# Power_Switching_Circuit_rev2.net
KiCad netlist of a schematic drawn in EAGLE
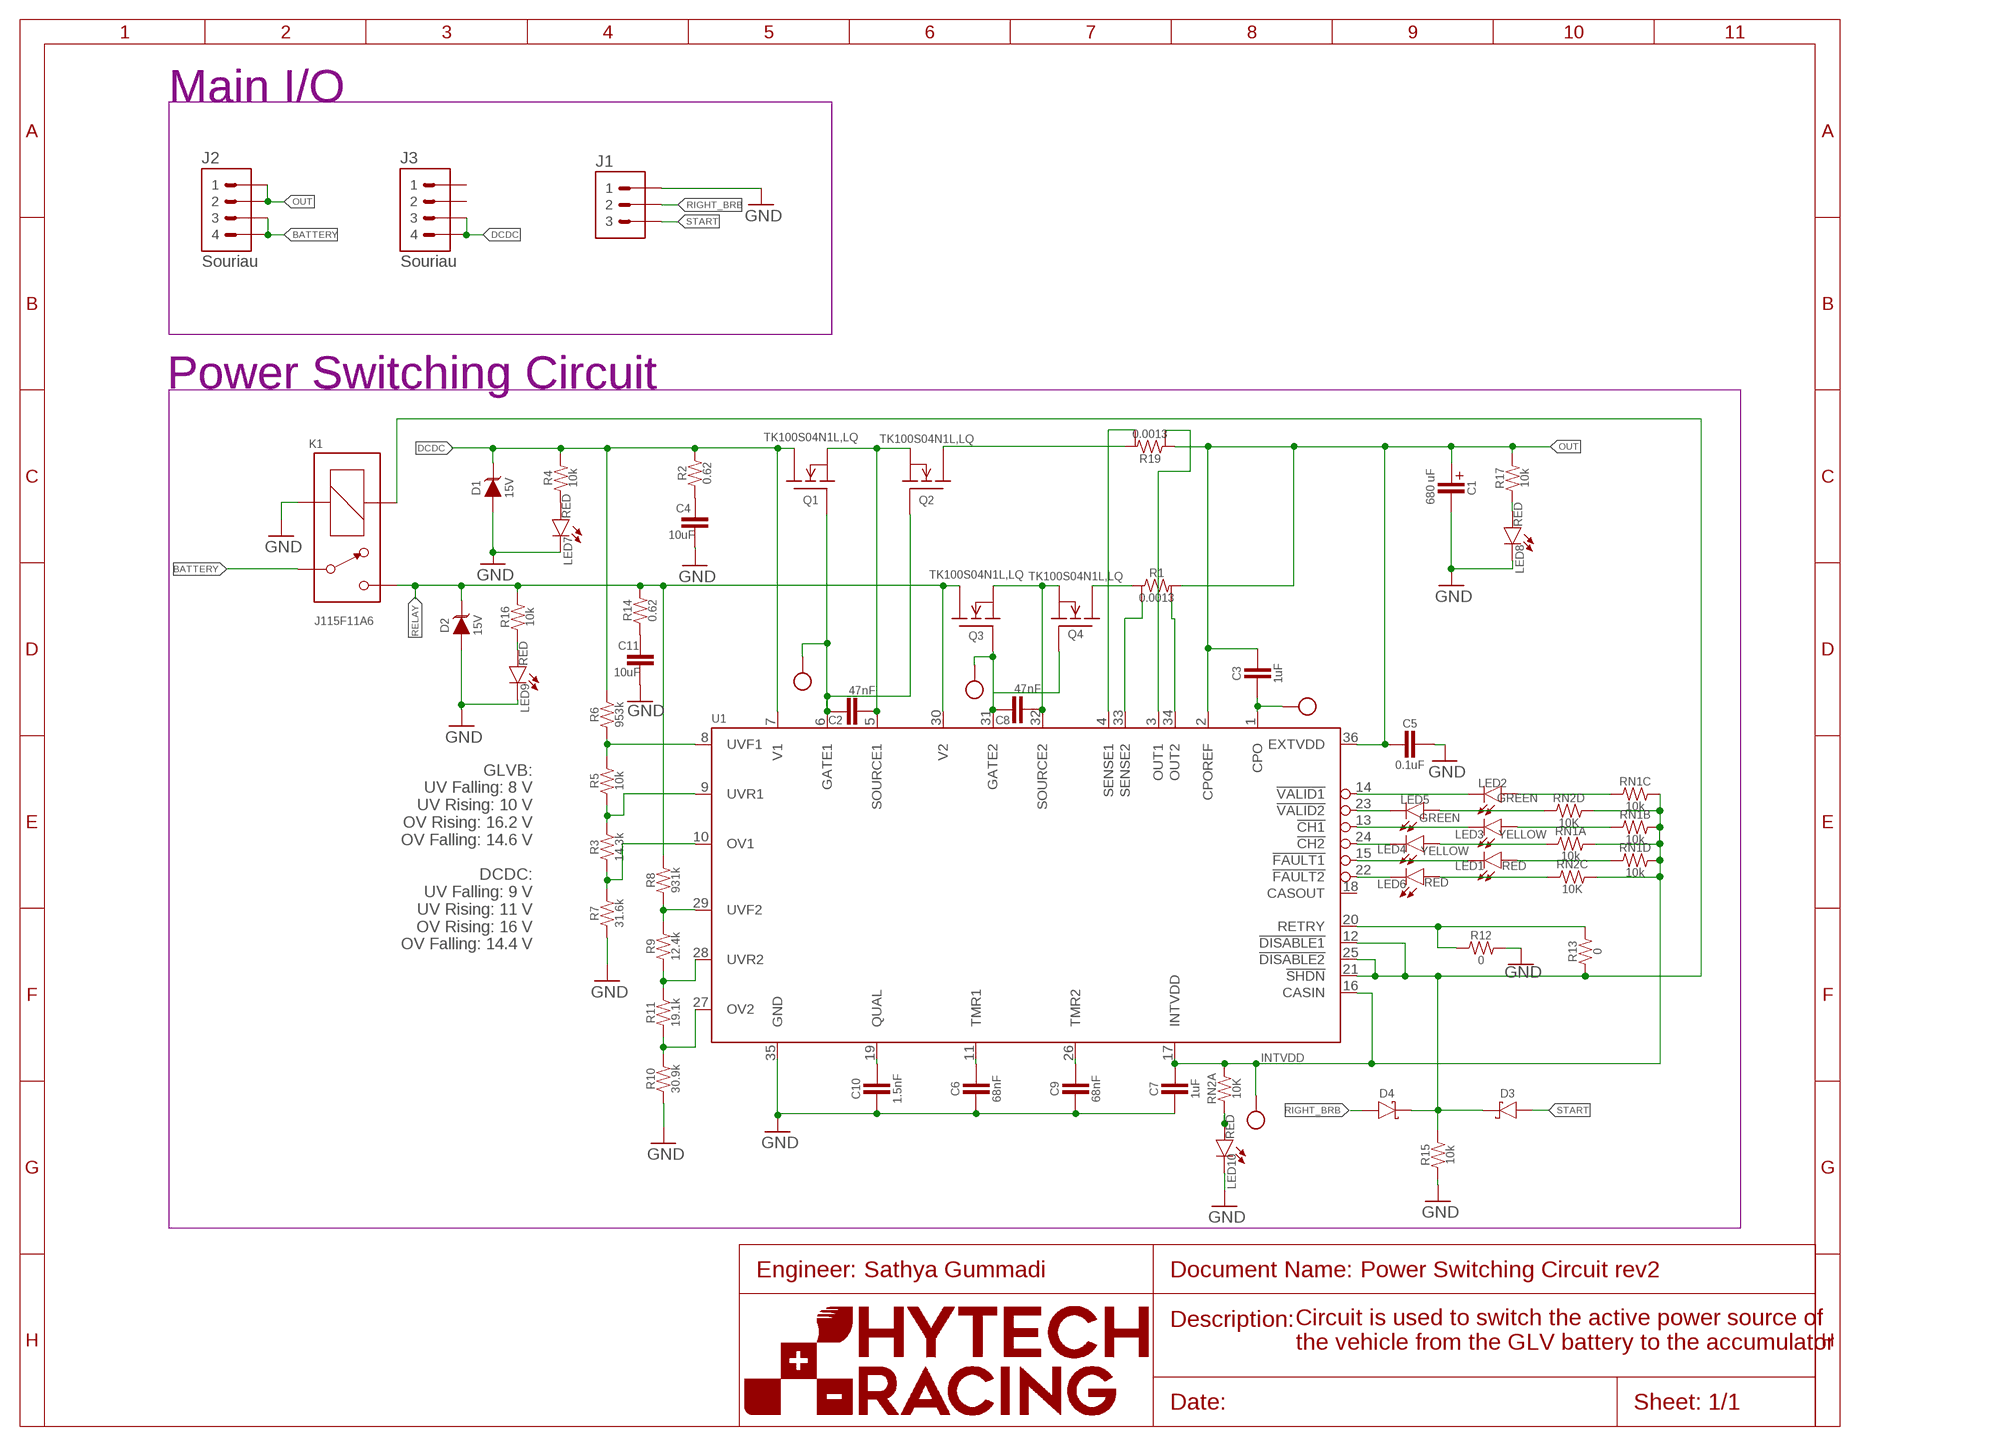
[diagram p0: schematic, sheet 1]

(export (version "E")
  (design (tool "Eeschema 10.0.6"))
  (components
    (comp (ref "C1")
      (value "CAPACITOR_POLARIZED")
      (footprint "eagle-import:EEE-FK1H681AM")
      (libsource (lib "eagle-import") (part "CAPACITOR_POLARIZED"))
    )
    (comp (ref "C2")
      (value "47nF")
      (footprint "eagle-import:0603-CAP@1")
      (libsource (lib "eagle-import") (part "CAP0603-CAP"))
    )
    (comp (ref "C3")
      (value "1uF")
      (footprint "eagle-import:0805")
      (libsource (lib "eagle-import") (part "CAP0805"))
    )
    (comp (ref "C4")
      (value "10uF")
      (footprint "eagle-import:1206-CAP")
      (libsource (lib "eagle-import") (part "CAPACITOR_VALUE1206"))
    )
    (comp (ref "C5")
      (value "0.1uF")
      (footprint "eagle-import:0603-CAP@1")
      (libsource (lib "eagle-import") (part "CAP0603-CAP"))
    )
    (comp (ref "C6")
      (value "68nF")
      (footprint "eagle-import:0603-CAP@1")
      (libsource (lib "eagle-import") (part "CAP0603-CAP"))
    )
    (comp (ref "C7")
      (value "1uF")
      (footprint "eagle-import:0805")
      (libsource (lib "eagle-import") (part "CAP0805"))
    )
    (comp (ref "C8")
      (value "47nF")
      (footprint "eagle-import:0603-CAP@1")
      (libsource (lib "eagle-import") (part "CAP0603-CAP"))
    )
    (comp (ref "C9")
      (value "68nF")
      (footprint "eagle-import:0603-CAP@1")
      (libsource (lib "eagle-import") (part "CAP0603-CAP"))
    )
    (comp (ref "C10")
      (value "1.5nF")
      (footprint "eagle-import:0603-CAP@1")
      (libsource (lib "eagle-import") (part "CAP0603-CAP"))
    )
    (comp (ref "C11")
      (value "10uF")
      (footprint "eagle-import:1206-CAP")
      (libsource (lib "eagle-import") (part "CAPACITOR_VALUE1206"))
    )
    (comp (ref "D1")
      (value "TVS_15V")
      (footprint "eagle-import:SOT-23")
      (fields
        (field (name "MANUFACTURER") "Vishay General Semiconductor - Diodes Division")
        (field (name "MPN") "GSOT15-E3-08")
        (field (name "VOLTAGE") "15V")
      )
      (libsource (lib "eagle-import") (part "TVS_15V"))
    )
    (comp (ref "D2")
      (value "TVS_15V")
      (footprint "eagle-import:SOT-23")
      (fields
        (field (name "MANUFACTURER") "Vishay General Semiconductor - Diodes Division")
        (field (name "MPN") "GSOT15-E3-08")
        (field (name "VOLTAGE") "15V")
      )
      (libsource (lib "eagle-import") (part "TVS_15V"))
    )
    (comp (ref "D3")
      (value "SCHOTTKY")
      (footprint "eagle-import:CLP1608-2L")
      (fields
        (field (name "MANUFACTURER") "Vishay General Semiconductor - Diodes Division")
        (field (name "MPN") "VSKY20401608-G4-08")
      )
      (libsource (lib "eagle-import") (part "SCHOTTKY"))
    )
    (comp (ref "D4")
      (value "SCHOTTKY")
      (footprint "eagle-import:CLP1608-2L")
      (fields
        (field (name "MANUFACTURER") "Vishay General Semiconductor - Diodes Division")
        (field (name "MPN") "VSKY20401608-G4-08")
      )
      (libsource (lib "eagle-import") (part "SCHOTTKY"))
    )
    (comp (ref "J1")
      (value "CONNECTOR-3_")
      (footprint "eagle-import:SOURIAU_04-35")
      (libsource (lib "eagle-import") (part "CONNECTOR-3_?"))
    )
    (comp (ref "J2")
      (value "CONNECTOR-4_SOURIAU_")
      (footprint "eagle-import:SOURIAU_12-04")
      (fields
        (field (name "MODEL") "Souriau")
        (field (name "MANUFACTURER") "Souriau")
        (field (name "MPN") "8STA21204PN ")
      )
      (libsource (lib "eagle-import") (part "CONNECTOR-4_?_SOURIAU"))
    )
    (comp (ref "J3")
      (value "CONNECTOR-4_SOURIAU_")
      (footprint "eagle-import:SOURIAU_12-04")
      (fields
        (field (name "MODEL") "Souriau")
        (field (name "MANUFACTURER") "Souriau")
        (field (name "MPN") "8STA21204PN ")
      )
      (libsource (lib "eagle-import") (part "CONNECTOR-4_?_SOURIAU"))
    )
    (comp (ref "K1")
      (value "J115F11A6")
      (footprint "eagle-import:J115F11A_6_")
      (libsource (lib "eagle-import") (part "J115F11A6"))
    )
    (comp (ref "LED1")
      (value "RED")
      (footprint "eagle-import:LED-603")
      (libsource (lib "eagle-import") (part "LED-0603"))
    )
    (comp (ref "LED2")
      (value "GREEN")
      (footprint "eagle-import:LED-603")
      (libsource (lib "eagle-import") (part "LED-0603"))
    )
    (comp (ref "LED3")
      (value "YELLOW")
      (footprint "eagle-import:LED-603")
      (libsource (lib "eagle-import") (part "LED-0603"))
    )
    (comp (ref "LED4")
      (value "YELLOW")
      (footprint "eagle-import:LED-603")
      (libsource (lib "eagle-import") (part "LED-0603"))
    )
    (comp (ref "LED5")
      (value "GREEN")
      (footprint "eagle-import:LED-603")
      (libsource (lib "eagle-import") (part "LED-0603"))
    )
    (comp (ref "LED6")
      (value "RED")
      (footprint "eagle-import:LED-603")
      (libsource (lib "eagle-import") (part "LED-0603"))
    )
    (comp (ref "LED7")
      (value "RED")
      (footprint "eagle-import:LED-603")
      (libsource (lib "eagle-import") (part "LED-0603"))
    )
    (comp (ref "LED8")
      (value "RED")
      (footprint "eagle-import:LED-603")
      (libsource (lib "eagle-import") (part "LED-0603"))
    )
    (comp (ref "LED9")
      (value "RED")
      (footprint "eagle-import:LED-603")
      (libsource (lib "eagle-import") (part "LED-0603"))
    )
    (comp (ref "LED10")
      (value "RED")
      (footprint "eagle-import:LED-603")
      (libsource (lib "eagle-import") (part "LED-0603"))
    )
    (comp (ref "Q1")
      (value "TK100S04N1L")
      (footprint "eagle-import:TO-252-3")
      (fields (field (name "MPN") "TK100S04N1L,LQ"))
      (libsource (lib "eagle-import") (part "TK100S04N1L"))
    )
    (comp (ref "Q2")
      (value "TK100S04N1L")
      (footprint "eagle-import:TO-252-3")
      (fields (field (name "MPN") "TK100S04N1L,LQ"))
      (libsource (lib "eagle-import") (part "TK100S04N1L"))
    )
    (comp (ref "Q3")
      (value "TK100S04N1L")
      (footprint "eagle-import:TO-252-3")
      (fields (field (name "MPN") "TK100S04N1L,LQ"))
      (libsource (lib "eagle-import") (part "TK100S04N1L"))
    )
    (comp (ref "Q4")
      (value "TK100S04N1L")
      (footprint "eagle-import:TO-252-3")
      (fields (field (name "MPN") "TK100S04N1L,LQ"))
      (libsource (lib "eagle-import") (part "TK100S04N1L"))
    )
    (comp (ref "R1")
      (value "RESISTOR_SENSE")
      (footprint "eagle-import:WSL2726")
      (fields (field (name "RESISTANCE") "0.0013") (field (name "MPN") "WSL2726"))
      (libsource (lib "eagle-import") (part "RESISTOR_SENSE"))
    )
    (comp (ref "R2")
      (value "0.62")
      (footprint "eagle-import:0805")
      (libsource (lib "eagle-import") (part "RESISTOR0805"))
    )
    (comp (ref "R3")
      (value "14.3k")
      (footprint "eagle-import:0603-RES")
      (libsource (lib "eagle-import") (part "RESISTOR0603"))
    )
    (comp (ref "R4")
      (value "10k")
      (footprint "eagle-import:0603-RES")
      (libsource (lib "eagle-import") (part "RESISTOR0603"))
    )
    (comp (ref "R5")
      (value "10k")
      (footprint "eagle-import:0603-RES")
      (libsource (lib "eagle-import") (part "RESISTOR0603"))
    )
    (comp (ref "R6")
      (value "953k")
      (footprint "eagle-import:0603-RES")
      (libsource (lib "eagle-import") (part "RESISTOR0603"))
    )
    (comp (ref "R7")
      (value "31.6k")
      (footprint "eagle-import:0603-RES")
      (libsource (lib "eagle-import") (part "RESISTOR0603"))
    )
    (comp (ref "R8")
      (value "931k")
      (footprint "eagle-import:0603-RES")
      (libsource (lib "eagle-import") (part "RESISTOR0603"))
    )
    (comp (ref "R9")
      (value "12.4k")
      (footprint "eagle-import:0603-RES")
      (libsource (lib "eagle-import") (part "RESISTOR0603"))
    )
    (comp (ref "R10")
      (value "30.9k")
      (footprint "eagle-import:0603-RES")
      (libsource (lib "eagle-import") (part "RESISTOR0603"))
    )
    (comp (ref "R11")
      (value "19.1k")
      (footprint "eagle-import:0603-RES")
      (libsource (lib "eagle-import") (part "RESISTOR0603"))
    )
    (comp (ref "R12")
      (value "0")
      (footprint "eagle-import:0603-RES")
      (libsource (lib "eagle-import") (part "RESISTOR0603"))
    )
    (comp (ref "R13")
      (value "0")
      (footprint "eagle-import:0603-RES")
      (libsource (lib "eagle-import") (part "RESISTOR0603"))
    )
    (comp (ref "R14")
      (value "0.62")
      (footprint "eagle-import:0805")
      (libsource (lib "eagle-import") (part "RESISTOR0805"))
    )
    (comp (ref "R15")
      (value "10k")
      (footprint "eagle-import:0603-RES")
      (libsource (lib "eagle-import") (part "RESISTOR0603"))
    )
    (comp (ref "R16")
      (value "10k")
      (footprint "eagle-import:0603-RES")
      (libsource (lib "eagle-import") (part "RESISTOR0603"))
    )
    (comp (ref "R17")
      (value "10k")
      (footprint "eagle-import:0603-RES")
      (libsource (lib "eagle-import") (part "RESISTOR0603"))
    )
    (comp (ref "R19")
      (value "RESISTOR_SENSE")
      (footprint "eagle-import:WSL2726")
      (fields (field (name "RESISTANCE") "0.0013") (field (name "MPN") "WSL2726"))
      (libsource (lib "eagle-import") (part "RESISTOR_SENSE"))
    )
    (comp (ref "RN1")
      (value "RESISTOR_NETWORK_4_10K")
      (footprint "eagle-import:YC_TC164")
      (fields (field (name "RESISTANCE") "10k"))
      (libsource (lib "eagle-import") (part "HyTechDevices - Copy_RESISTOR_NETWORK_4_10K"))
    )
    (comp (ref "RN2")
      (value "RESISTOR_NETWORK_4_10K")
      (footprint "eagle-import:1206-RES")
      (fields
        (field (name "MANUFACTURER") "Yageo")
        (field (name "MPN") "TC164-FR-0710KL")
        (field (name "POWER") "1/16W")
        (field (name "RESISTANCE") "10K")
      )
      (libsource (lib "eagle-import") (part "RESISTOR_NETWORK_4_10K"))
    )
    (comp (ref "U$7")
      (value "TEST_POINTMICRO_MINIATURE")
      (footprint "eagle-import:MICRO_MINIATURE")
      (libsource (lib "eagle-import") (part "TEST_POINTMICRO_MINIATURE"))
    )
    (comp (ref "U$8")
      (value "TEST_POINTMICRO_MINIATURE")
      (footprint "eagle-import:MICRO_MINIATURE")
      (libsource (lib "eagle-import") (part "TEST_POINTMICRO_MINIATURE"))
    )
    (comp (ref "U$9")
      (value "TEST_POINTMICRO_MINIATURE")
      (footprint "eagle-import:MICRO_MINIATURE")
      (libsource (lib "eagle-import") (part "TEST_POINTMICRO_MINIATURE"))
    )
    (comp (ref "U$10")
      (value "TEST_POINTMICRO_MINIATURE")
      (footprint "eagle-import:MICRO_MINIATURE")
      (libsource (lib "eagle-import") (part "TEST_POINTMICRO_MINIATURE"))
    )
    (comp (ref "U1")
      (value "LTC4421")
      (footprint "eagle-import:SSOP-36")
      (libsource (lib "eagle-import") (part "LTC4421"))
    )
  )
  (nets
    (net (code "1") (name "/INTVDD") (class "Default")
      (node (ref "C7") (pin "1") (pinfunction "1_1") (pintype "passive"))
      (node (ref "RN1") (pin "5") (pinfunction "2_5") (pintype "passive"))
      (node (ref "RN1") (pin "6") (pinfunction "2_6") (pintype "passive"))
      (node (ref "RN1") (pin "7") (pinfunction "2_7") (pintype "passive"))
      (node (ref "RN1") (pin "8") (pinfunction "2_8") (pintype "passive"))
      (node (ref "RN2") (pin "5") (pinfunction "2_5") (pintype "passive"))
      (node (ref "RN2") (pin "6") (pinfunction "2_6") (pintype "passive"))
      (node (ref "RN2") (pin "8") (pinfunction "2_8") (pintype "passive"))
      (node (ref "U$8") (pin "P$1") (pinfunction "P$1_P$1") (pintype "bidirectional"))
      (node (ref "U1") (pin "16") (pinfunction "CASIN_16") (pintype "input"))
      (node (ref "U1") (pin "17") (pinfunction "INTVDD_17") (pintype "power_in"))
    )
    (net (code "2") (name "BATTERY") (class "Default")
      (node (ref "J2") (pin "3") (pinfunction "3_3") (pintype "passive"))
      (node (ref "J2") (pin "4") (pinfunction "4_4") (pintype "passive"))
      (node (ref "K1") (pin "CONTACT1") (pinfunction "P_CONTACT1") (pintype "bidirectional"))
    )
    (net (code "3") (name "DCDC") (class "Default")
      (node (ref "D1") (pin "3") (pinfunction "C_3") (pintype "passive"))
      (node (ref "J3") (pin "3") (pinfunction "3_3") (pintype "passive"))
      (node (ref "J3") (pin "4") (pinfunction "4_4") (pintype "passive"))
      (node (ref "Q1") (pin "2") (pinfunction "D_2") (pintype "passive"))
      (node (ref "R2") (pin "2") (pinfunction "2_2") (pintype "passive"))
      (node (ref "R4") (pin "2") (pinfunction "2_2") (pintype "passive"))
      (node (ref "R6") (pin "2") (pinfunction "2_2") (pintype "passive"))
      (node (ref "U1") (pin "7") (pinfunction "V1_7") (pintype "input"))
    )
    (net (code "4") (name "GND") (class "Default")
      (node (ref "C1") (pin "P$2") (pinfunction "MINUS_P$2") (pintype "passive"))
      (node (ref "C10") (pin "2") (pinfunction "2_2") (pintype "passive"))
      (node (ref "C11") (pin "2") (pinfunction "2_2") (pintype "passive"))
      (node (ref "C4") (pin "2") (pinfunction "2_2") (pintype "passive"))
      (node (ref "C5") (pin "1") (pinfunction "1_1") (pintype "passive"))
      (node (ref "C6") (pin "2") (pinfunction "2_2") (pintype "passive"))
      (node (ref "C7") (pin "2") (pinfunction "2_2") (pintype "passive"))
      (node (ref "C9") (pin "2") (pinfunction "2_2") (pintype "passive"))
      (node (ref "D1") (pin "1") (pinfunction "A_1") (pintype "passive"))
      (node (ref "D2") (pin "1") (pinfunction "A_1") (pintype "passive"))
      (node (ref "J1") (pin "A") (pinfunction "1_A") (pintype "passive"))
      (node (ref "K1") (pin "COIL2") (pinfunction "COIL-_COIL2") (pintype "bidirectional"))
      (node (ref "LED10") (pin "C") (pinfunction "C_C") (pintype "passive"))
      (node (ref "LED7") (pin "C") (pinfunction "C_C") (pintype "passive"))
      (node (ref "LED8") (pin "C") (pinfunction "C_C") (pintype "passive"))
      (node (ref "LED9") (pin "C") (pinfunction "C_C") (pintype "passive"))
      (node (ref "R10") (pin "1") (pinfunction "1_1") (pintype "passive"))
      (node (ref "R12") (pin "2") (pinfunction "2_2") (pintype "passive"))
      (node (ref "R15") (pin "1") (pinfunction "1_1") (pintype "passive"))
      (node (ref "R7") (pin "1") (pinfunction "1_1") (pintype "passive"))
      (node (ref "U1") (pin "35") (pinfunction "GND_35") (pintype "power_in"))
    )
    (net (code "5") (name "Net-(C4-Pad1)") (class "Default")
      (node (ref "C4") (pin "1") (pinfunction "1_1") (pintype "passive"))
      (node (ref "R2") (pin "1") (pinfunction "1_1") (pintype "passive"))
    )
    (net (code "6") (name "Net-(C11-Pad1)") (class "Default")
      (node (ref "C11") (pin "1") (pinfunction "1_1") (pintype "passive"))
      (node (ref "R14") (pin "1") (pinfunction "1_1") (pintype "passive"))
    )
    (net (code "7") (name "Net-(D3-C)") (class "Default")
      (node (ref "D3") (pin "2") (pinfunction "C_2") (pintype "passive"))
      (node (ref "D4") (pin "2") (pinfunction "C_2") (pintype "passive"))
      (node (ref "K1") (pin "COIL1") (pinfunction "COIL+_COIL1") (pintype "bidirectional"))
      (node (ref "R13") (pin "1") (pinfunction "1_1") (pintype "passive"))
      (node (ref "R15") (pin "2") (pinfunction "2_2") (pintype "passive"))
      (node (ref "U1") (pin "12") (pinfunction "~{DISABLE1}_12") (pintype "input"))
      (node (ref "U1") (pin "21") (pinfunction "~{SHDN}_21") (pintype "input"))
      (node (ref "U1") (pin "25") (pinfunction "~{DISABLE2}_25") (pintype "input"))
    )
    (net (code "8") (name "Net-(LED4-PadA)") (class "Default")
      (node (ref "LED4") (pin "A") (pinfunction "A_A") (pintype "passive"))
      (node (ref "RN1") (pin "1") (pinfunction "1_1") (pintype "passive"))
    )
    (net (code "9") (name "Net-(LED7-PadA)") (class "Default")
      (node (ref "LED7") (pin "A") (pinfunction "A_A") (pintype "passive"))
      (node (ref "R4") (pin "1") (pinfunction "1_1") (pintype "passive"))
    )
    (net (code "10") (name "Net-(LED8-PadA)") (class "Default")
      (node (ref "LED8") (pin "A") (pinfunction "A_A") (pintype "passive"))
      (node (ref "R17") (pin "1") (pinfunction "1_1") (pintype "passive"))
    )
    (net (code "11") (name "Net-(LED9-PadA)") (class "Default")
      (node (ref "LED9") (pin "A") (pinfunction "A_A") (pintype "passive"))
      (node (ref "R16") (pin "1") (pinfunction "1_1") (pintype "passive"))
    )
    (net (code "12") (name "Net-(LED10-PadA)") (class "Default")
      (node (ref "LED10") (pin "A") (pinfunction "A_A") (pintype "passive"))
      (node (ref "RN2") (pin "1") (pinfunction "1_1") (pintype "passive"))
    )
    (net (code "13") (name "Net-(Q1-G)") (class "Default")
      (node (ref "C2") (pin "2") (pinfunction "2_2") (pintype "passive"))
      (node (ref "Q1") (pin "1") (pinfunction "G_1") (pintype "passive"))
      (node (ref "Q2") (pin "1") (pinfunction "G_1") (pintype "passive"))
      (node (ref "U$10") (pin "P$1") (pinfunction "P$1_P$1") (pintype "bidirectional"))
      (node (ref "U1") (pin "6") (pinfunction "GATE1_6") (pintype "input"))
    )
    (net (code "14") (name "Net-(Q1-S)") (class "Default")
      (node (ref "C2") (pin "1") (pinfunction "1_1") (pintype "passive"))
      (node (ref "Q1") (pin "3") (pinfunction "S_3") (pintype "passive"))
      (node (ref "Q2") (pin "3") (pinfunction "S_3") (pintype "passive"))
      (node (ref "U1") (pin "5") (pinfunction "SOURCE1_5") (pintype "input"))
    )
    (net (code "15") (name "Net-(Q2-D)") (class "Default")
      (node (ref "Q2") (pin "2") (pinfunction "D_2") (pintype "passive"))
      (node (ref "R19") (pin "2") (pinfunction "2_2") (pintype "passive"))
    )
    (net (code "16") (name "Net-(Q3-G)") (class "Default")
      (node (ref "C8") (pin "2") (pinfunction "2_2") (pintype "passive"))
      (node (ref "Q3") (pin "1") (pinfunction "G_1") (pintype "passive"))
      (node (ref "Q4") (pin "1") (pinfunction "G_1") (pintype "passive"))
      (node (ref "U$7") (pin "P$1") (pinfunction "P$1_P$1") (pintype "bidirectional"))
      (node (ref "U1") (pin "31") (pinfunction "GATE2_31") (pintype "input"))
    )
    (net (code "17") (name "Net-(Q3-S)") (class "Default")
      (node (ref "C8") (pin "1") (pinfunction "1_1") (pintype "passive"))
      (node (ref "Q3") (pin "3") (pinfunction "S_3") (pintype "passive"))
      (node (ref "Q4") (pin "3") (pinfunction "S_3") (pintype "passive"))
      (node (ref "U1") (pin "32") (pinfunction "SOURCE2_32") (pintype "input"))
    )
    (net (code "18") (name "Net-(Q4-D)") (class "Default")
      (node (ref "Q4") (pin "2") (pinfunction "D_2") (pintype "passive"))
      (node (ref "R1") (pin "1") (pinfunction "1_1") (pintype "passive"))
    )
    (net (code "19") (name "Net-(RN1B-1)") (class "Default")
      (node (ref "LED3") (pin "A") (pinfunction "A_A") (pintype "passive"))
      (node (ref "RN1") (pin "2") (pinfunction "1_2") (pintype "passive"))
    )
    (net (code "20") (name "Net-(RN1C-1)") (class "Default")
      (node (ref "LED2") (pin "A") (pinfunction "A_A") (pintype "passive"))
      (node (ref "RN1") (pin "3") (pinfunction "1_3") (pintype "passive"))
    )
    (net (code "21") (name "Net-(RN1D-1)") (class "Default")
      (node (ref "LED1") (pin "A") (pinfunction "A_A") (pintype "passive"))
      (node (ref "RN1") (pin "4") (pinfunction "1_4") (pintype "passive"))
    )
    (net (code "22") (name "Net-(RN2C-1)") (class "Default")
      (node (ref "LED6") (pin "A") (pinfunction "A_A") (pintype "passive"))
      (node (ref "RN2") (pin "3") (pinfunction "1_3") (pintype "passive"))
    )
    (net (code "23") (name "Net-(RN2D-1)") (class "Default")
      (node (ref "LED5") (pin "A") (pinfunction "A_A") (pintype "passive"))
      (node (ref "RN2") (pin "4") (pinfunction "1_4") (pintype "passive"))
    )
    (net (code "24") (name "Net-(U1-CPO)") (class "Default")
      (node (ref "C3") (pin "2") (pinfunction "2_2") (pintype "passive"))
      (node (ref "U$9") (pin "P$1") (pinfunction "P$1_P$1") (pintype "bidirectional"))
      (node (ref "U1") (pin "1") (pinfunction "CPO_1") (pintype "input"))
    )
    (net (code "25") (name "Net-(U1-OUT1)") (class "Default")
      (node (ref "R19") (pin "3") (pinfunction "3_3") (pintype "passive"))
      (node (ref "U1") (pin "3") (pinfunction "OUT1_3") (pintype "input"))
    )
    (net (code "26") (name "Net-(U1-OUT2)") (class "Default")
      (node (ref "R1") (pin "4") (pinfunction "4_4") (pintype "passive"))
      (node (ref "U1") (pin "34") (pinfunction "OUT2_34") (pintype "input"))
    )
    (net (code "27") (name "Net-(U1-OV1)") (class "Default")
      (node (ref "R3") (pin "1") (pinfunction "1_1") (pintype "passive"))
      (node (ref "R7") (pin "2") (pinfunction "2_2") (pintype "passive"))
      (node (ref "U1") (pin "10") (pinfunction "OV1_10") (pintype "input"))
    )
    (net (code "28") (name "Net-(U1-OV2)") (class "Default")
      (node (ref "R10") (pin "2") (pinfunction "2_2") (pintype "passive"))
      (node (ref "R11") (pin "1") (pinfunction "1_1") (pintype "passive"))
      (node (ref "U1") (pin "27") (pinfunction "OV2_27") (pintype "input"))
    )
    (net (code "29") (name "Net-(U1-QUAL)") (class "Default")
      (node (ref "C10") (pin "1") (pinfunction "1_1") (pintype "passive"))
      (node (ref "U1") (pin "19") (pinfunction "QUAL_19") (pintype "bidirectional"))
    )
    (net (code "30") (name "Net-(U1-RETRY)") (class "Default")
      (node (ref "R12") (pin "1") (pinfunction "1_1") (pintype "passive"))
      (node (ref "R13") (pin "2") (pinfunction "2_2") (pintype "passive"))
      (node (ref "U1") (pin "20") (pinfunction "RETRY_20") (pintype "input"))
    )
    (net (code "31") (name "Net-(U1-SENSE1)") (class "Default")
      (node (ref "R19") (pin "4") (pinfunction "4_4") (pintype "passive"))
      (node (ref "U1") (pin "4") (pinfunction "SENSE1_4") (pintype "input"))
    )
    (net (code "32") (name "Net-(U1-SENSE2)") (class "Default")
      (node (ref "R1") (pin "3") (pinfunction "3_3") (pintype "passive"))
      (node (ref "U1") (pin "33") (pinfunction "SENSE2_33") (pintype "input"))
    )
    (net (code "33") (name "Net-(U1-TMR1)") (class "Default")
      (node (ref "C6") (pin "1") (pinfunction "1_1") (pintype "passive"))
      (node (ref "U1") (pin "11") (pinfunction "TMR1_11") (pintype "bidirectional"))
    )
    (net (code "34") (name "Net-(U1-TMR2)") (class "Default")
      (node (ref "C9") (pin "1") (pinfunction "1_1") (pintype "passive"))
      (node (ref "U1") (pin "26") (pinfunction "TMR2_26") (pintype "bidirectional"))
    )
    (net (code "35") (name "Net-(U1-UVF1)") (class "Default")
      (node (ref "R5") (pin "2") (pinfunction "2_2") (pintype "passive"))
      (node (ref "R6") (pin "1") (pinfunction "1_1") (pintype "passive"))
      (node (ref "U1") (pin "8") (pinfunction "UVF1_8") (pintype "input"))
    )
    (net (code "36") (name "Net-(U1-UVF2)") (class "Default")
      (node (ref "R8") (pin "1") (pinfunction "1_1") (pintype "passive"))
      (node (ref "R9") (pin "2") (pinfunction "2_2") (pintype "passive"))
      (node (ref "U1") (pin "29") (pinfunction "UVF2_29") (pintype "input"))
    )
    (net (code "37") (name "Net-(U1-UVR1)") (class "Default")
      (node (ref "R3") (pin "2") (pinfunction "2_2") (pintype "passive"))
      (node (ref "R5") (pin "1") (pinfunction "1_1") (pintype "passive"))
      (node (ref "U1") (pin "9") (pinfunction "UVR1_9") (pintype "input"))
    )
    (net (code "38") (name "Net-(U1-UVR2)") (class "Default")
      (node (ref "R11") (pin "2") (pinfunction "2_2") (pintype "passive"))
      (node (ref "R9") (pin "1") (pinfunction "1_1") (pintype "passive"))
      (node (ref "U1") (pin "28") (pinfunction "UVR2_28") (pintype "input"))
    )
    (net (code "39") (name "Net-(U1-~{CH1})") (class "Default")
      (node (ref "LED3") (pin "C") (pinfunction "C_C") (pintype "passive"))
      (node (ref "U1") (pin "13") (pinfunction "~{CH1}_13") (pintype "open_collector"))
    )
    (net (code "40") (name "Net-(U1-~{CH2})") (class "Default")
      (node (ref "LED4") (pin "C") (pinfunction "C_C") (pintype "passive"))
      (node (ref "U1") (pin "24") (pinfunction "~{CH2}_24") (pintype "open_collector"))
    )
    (net (code "41") (name "Net-(U1-~{FAULT1})") (class "Default")
      (node (ref "LED1") (pin "C") (pinfunction "C_C") (pintype "passive"))
      (node (ref "U1") (pin "15") (pinfunction "~{FAULT1}_15") (pintype "open_collector"))
    )
    (net (code "42") (name "Net-(U1-~{FAULT2})") (class "Default")
      (node (ref "LED6") (pin "C") (pinfunction "C_C") (pintype "passive"))
      (node (ref "U1") (pin "22") (pinfunction "~{FAULT2}_22") (pintype "open_collector"))
    )
    (net (code "43") (name "Net-(U1-~{VALID1})") (class "Default")
      (node (ref "LED2") (pin "C") (pinfunction "C_C") (pintype "passive"))
      (node (ref "U1") (pin "14") (pinfunction "~{VALID1}_14") (pintype "open_collector"))
    )
    (net (code "44") (name "Net-(U1-~{VALID2})") (class "Default")
      (node (ref "LED5") (pin "C") (pinfunction "C_C") (pintype "passive"))
      (node (ref "U1") (pin "23") (pinfunction "~{VALID2}_23") (pintype "open_collector"))
    )
    (net (code "45") (name "OUT") (class "Default")
      (node (ref "C1") (pin "P$1") (pinfunction "PLUS_P$1") (pintype "passive"))
      (node (ref "C3") (pin "1") (pinfunction "1_1") (pintype "passive"))
      (node (ref "C5") (pin "2") (pinfunction "2_2") (pintype "passive"))
      (node (ref "J2") (pin "1") (pinfunction "1_1") (pintype "passive"))
      (node (ref "J2") (pin "2") (pinfunction "2_2") (pintype "passive"))
      (node (ref "R1") (pin "2") (pinfunction "2_2") (pintype "passive"))
      (node (ref "R17") (pin "2") (pinfunction "2_2") (pintype "passive"))
      (node (ref "R19") (pin "1") (pinfunction "1_1") (pintype "passive"))
      (node (ref "U1") (pin "2") (pinfunction "CPOREF_2") (pintype "input"))
      (node (ref "U1") (pin "36") (pinfunction "EXTVDD_36") (pintype "power_in"))
    )
    (net (code "46") (name "RELAY") (class "Default")
      (node (ref "D2") (pin "3") (pinfunction "C_3") (pintype "passive"))
      (node (ref "K1") (pin "CONTACT2") (pinfunction "S_CONTACT2") (pintype "bidirectional"))
      (node (ref "Q3") (pin "2") (pinfunction "D_2") (pintype "passive"))
      (node (ref "R14") (pin "2") (pinfunction "2_2") (pintype "passive"))
      (node (ref "R16") (pin "2") (pinfunction "2_2") (pintype "passive"))
      (node (ref "R8") (pin "2") (pinfunction "2_2") (pintype "passive"))
      (node (ref "U1") (pin "30") (pinfunction "V2_30") (pintype "input"))
    )
    (net (code "47") (name "RIGHT_BRB") (class "Default")
      (node (ref "D4") (pin "1") (pinfunction "A_1") (pintype "passive"))
      (node (ref "J1") (pin "B") (pinfunction "2_B") (pintype "passive"))
    )
    (net (code "48") (name "START") (class "Default")
      (node (ref "D3") (pin "1") (pinfunction "A_1") (pintype "passive"))
      (node (ref "J1") (pin "C") (pinfunction "3_C") (pintype "passive"))
    )
    (net (code "49") (name "unconnected-(J3-Pad1)") (class "Default")
      (node (ref "J3") (pin "1") (pinfunction "1_1") (pintype "passive"))
    )
    (net (code "50") (name "unconnected-(J3-Pad2)") (class "Default")
      (node (ref "J3") (pin "2") (pinfunction "2_2") (pintype "passive"))
    )
    (net (code "51") (name "unconnected-(U1-CASOUT-Pad18)") (class "Default")
      (node (ref "U1") (pin "18") (pinfunction "CASOUT_18") (pintype "output"))
    )
  )
)
